# Lasers_Drivers_Design_Pingu_X1_pingu.net
KiCad netlist of a schematic drawn in EAGLE
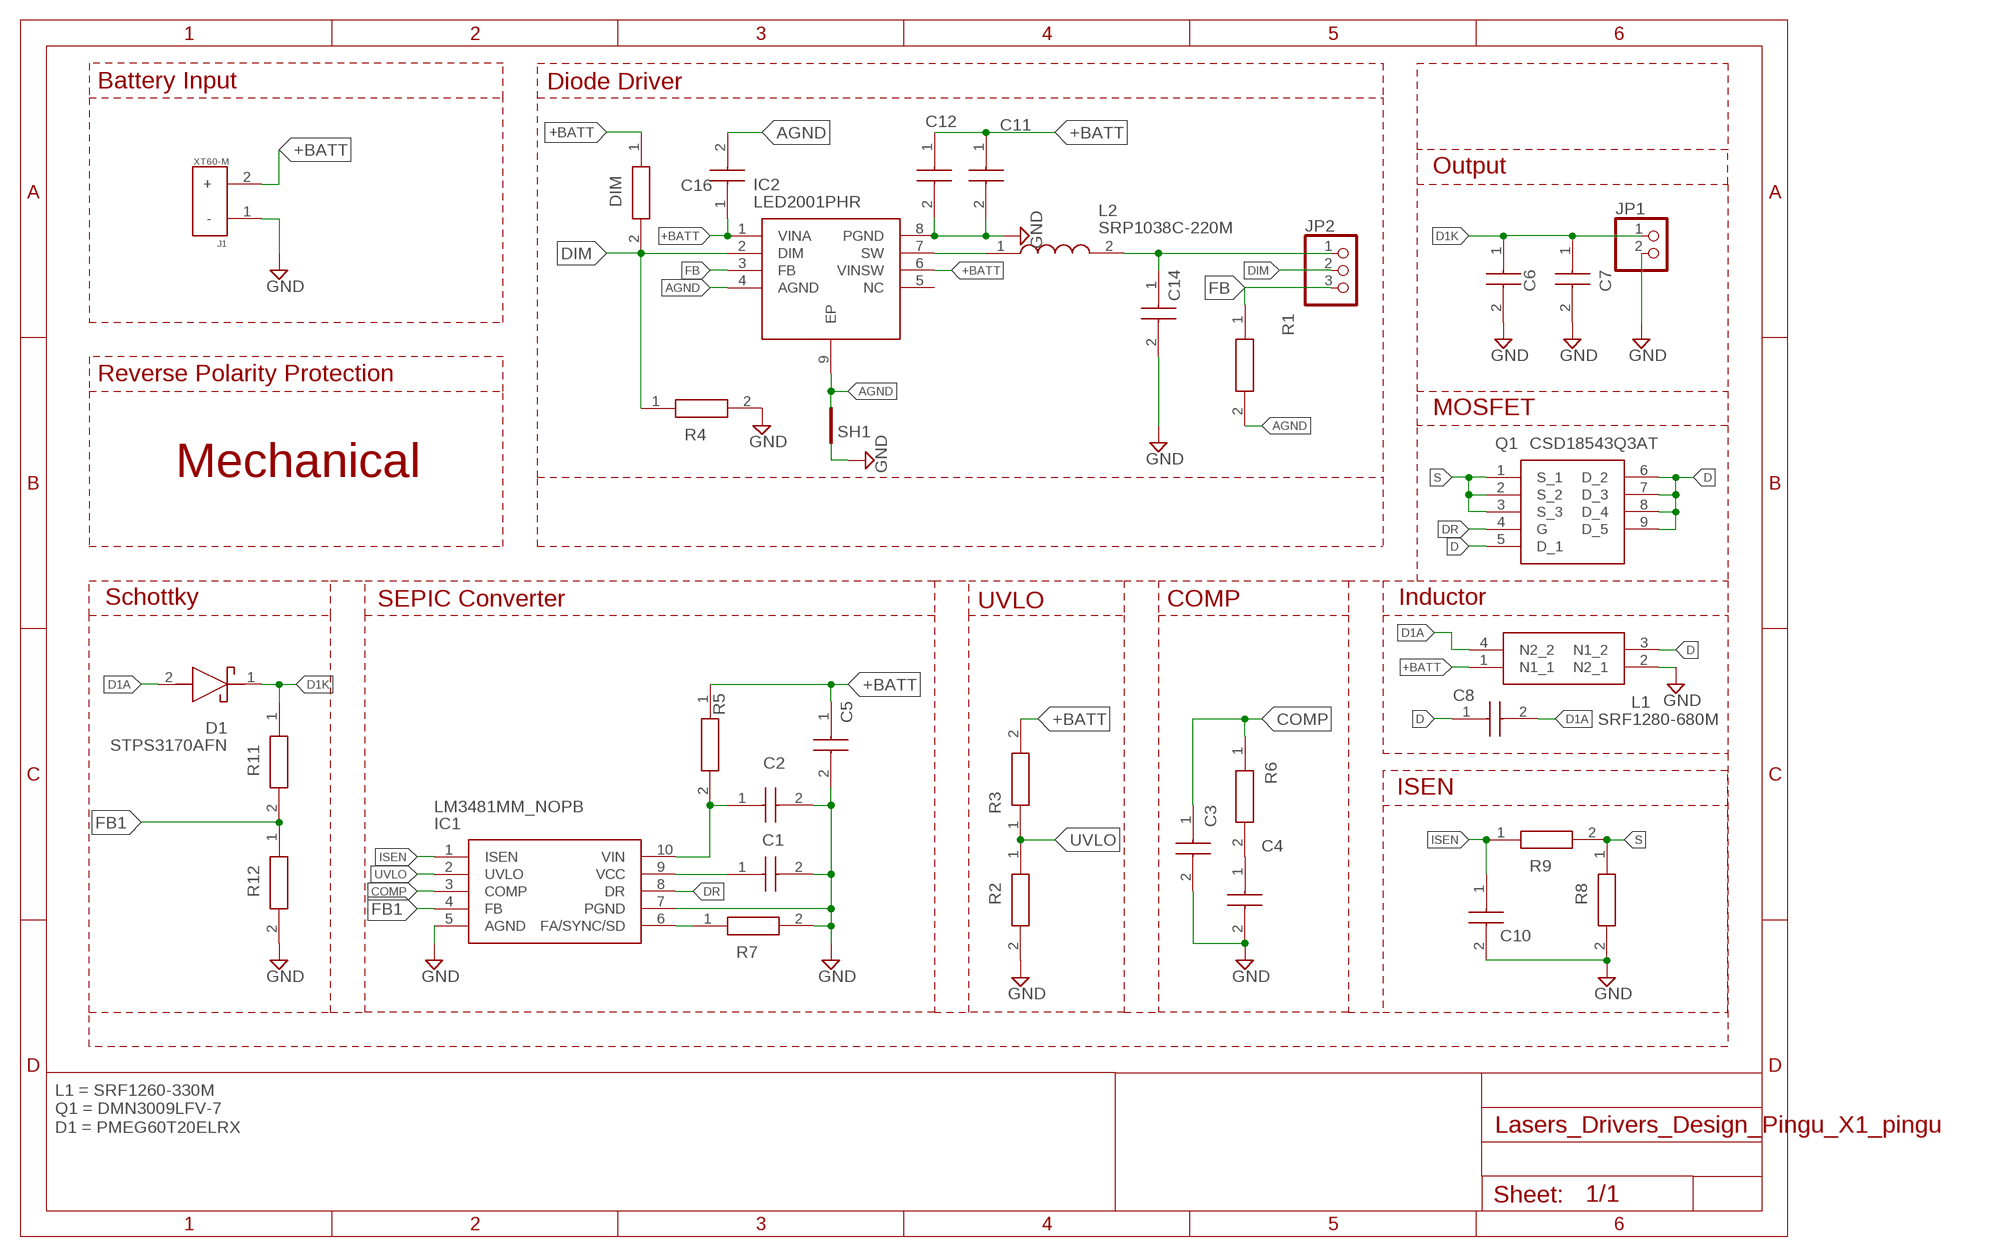
[diagram p0: schematic, sheet 1]

(export (version "E")
  (design (tool "Eeschema 10.0.6"))
  (components
    (comp (ref "C1")
      (value "GCM0335C1H8R0DA16J")
      (footprint "eagle-import:CAPC0603X33N")
      (fields (field (name "MOUSER_PART_NUMBER") "81-GCM0335C1H8R0DA6J"))
      (libsource (lib "eagle-import") (part "GCM0335C1H8R0DA16J"))
    )
    (comp (ref "C2")
      (value "GCM0335C1H8R0DA16J")
      (footprint "eagle-import:CAPC0603X33N")
      (fields (field (name "MOUSER_PART_NUMBER") "81-GCM0335C1H8R0DA6J"))
      (libsource (lib "eagle-import") (part "GCM0335C1H8R0DA16J"))
    )
    (comp (ref "C3")
      (value "GCM0335C1H8R0DA16J")
      (footprint "eagle-import:CAPC0603X33N")
      (fields (field (name "MOUSER_PART_NUMBER") "81-GCM0335C1H8R0DA6J"))
      (libsource (lib "eagle-import") (part "GCM0335C1H8R0DA16J"))
    )
    (comp (ref "C4")
      (value "GCM0335C1H8R0DA16J")
      (footprint "eagle-import:CAPC0603X33N")
      (fields (field (name "MOUSER_PART_NUMBER") "81-GCM0335C1H8R0DA6J"))
      (libsource (lib "eagle-import") (part "GCM0335C1H8R0DA16J"))
    )
    (comp (ref "C5")
      (value "C1206C475K5RACTU")
      (footprint "eagle-import:CAPC3216X180N")
      (fields (field (name "MOUSER_PART_NUMBER") "80-C1206C475K5R"))
      (libsource (lib "eagle-import") (part "C1206C475K5RACTU"))
    )
    (comp (ref "C6")
      (value "C1206C475K5RACTU")
      (footprint "eagle-import:CAPC3216X180N")
      (fields (field (name "MOUSER_PART_NUMBER") "80-C1206C475K5R"))
      (libsource (lib "eagle-import") (part "C1206C475K5RACTU"))
    )
    (comp (ref "C7")
      (value "C1206C475K5RACTU")
      (footprint "eagle-import:CAPC3216X180N")
      (fields (field (name "MOUSER_PART_NUMBER") "80-C1206C475K5R"))
      (libsource (lib "eagle-import") (part "C1206C475K5RACTU"))
    )
    (comp (ref "C8")
      (value "C1206C475K5RACTU")
      (footprint "eagle-import:CAPC3216X180N")
      (fields (field (name "MOUSER_PART_NUMBER") "80-C1206C475K5R"))
      (libsource (lib "eagle-import") (part "C1206C475K5RACTU"))
    )
    (comp (ref "C10")
      (value "GCM0335C1H8R0DA16J")
      (footprint "eagle-import:CAPC0603X33N")
      (fields (field (name "MOUSER_PART_NUMBER") "81-GCM0335C1H8R0DA6J"))
      (libsource (lib "eagle-import") (part "GCM0335C1H8R0DA16J"))
    )
    (comp (ref "C11")
      (value "GCM0335C1H8R0DA16J")
      (footprint "eagle-import:CAPC0603X33N")
      (fields (field (name "MOUSER_PART_NUMBER") "81-GCM0335C1H8R0DA6J"))
      (libsource (lib "eagle-import") (part "GCM0335C1H8R0DA16J"))
    )
    (comp (ref "C12")
      (value "GCM0335C1H8R0DA16J")
      (footprint "eagle-import:CAPC0603X33N")
      (fields (field (name "MOUSER_PART_NUMBER") "81-GCM0335C1H8R0DA6J"))
      (libsource (lib "eagle-import") (part "GCM0335C1H8R0DA16J"))
    )
    (comp (ref "C14")
      (value "C1206C475K5RACTU")
      (footprint "eagle-import:CAPC3216X180N")
      (fields (field (name "MOUSER_PART_NUMBER") "80-C1206C475K5R"))
      (libsource (lib "eagle-import") (part "C1206C475K5RACTU"))
    )
    (comp (ref "C16")
      (value "C1206C475K5RACTU")
      (footprint "eagle-import:CAPC3216X180N")
      (fields (field (name "MOUSER_PART_NUMBER") "80-C1206C475K5R"))
      (libsource (lib "eagle-import") (part "C1206C475K5RACTU"))
    )
    (comp (ref "D1")
      (value "STPS3170AFN")
      (footprint "eagle-import:SODFL5226X110N")
      (fields (field (name "MOUSER_PART_NUMBER") "511-STPS3170AFN"))
      (libsource (lib "eagle-import") (part "STPS3170AFN"))
    )
    (comp (ref "DIM")
      (value "ERJ-3BWFR100V")
      (footprint "eagle-import:RESC1608X55N")
      (fields (field (name "MOUSER_PART_NUMBER") "667-ERJ-3BWFR100V"))
      (libsource (lib "eagle-import") (part "ERJ-3BWFR100V"))
    )
    (comp (ref "IC1")
      (value "LM3481MM_NOPB")
      (footprint "eagle-import:SOP50P490X110-10N")
      (fields
        (field (name "ARROW_PART_NUMBER") "LM3481MM/NOPB")
        (field (name "MOUSER_PART_NUMBER") "926-LM3481MM/NOPB")
      )
      (libsource (lib "eagle-import") (part "LM3481MM_NOPB"))
    )
    (comp (ref "IC2")
      (value "LED2001PHR")
      (footprint "eagle-import:SOIC127P600X170-9N")
      (fields (field (name "MOUSER_PART_NUMBER") "511-LED2001PHR"))
      (libsource (lib "eagle-import") (part "LED2001PHR"))
    )
    (comp (ref "J1")
      (value "XT60-M")
      (footprint "eagle-import:AMASS_XT60-M")
      (fields (field (name "MF") "AMASS"))
      (libsource (lib "eagle-import") (part "XT60-M"))
    )
    (comp (ref "JP1")
      (value "PINHD-1X2")
      (footprint "eagle-import:1X02")
      (libsource (lib "eagle-import") (part "PINHD-1X2"))
    )
    (comp (ref "JP2")
      (value "PINHD-1X3")
      (footprint "eagle-import:1X03")
      (libsource (lib "eagle-import") (part "PINHD-1X3"))
    )
    (comp (ref "L1")
      (value "SRF1280-680M")
      (footprint "eagle-import:SRF1280680M")
      (fields (field (name "MOUSER_PART_NUMBER") "652-SRF1280-680M") (field (name "SPICEPREFIX") "E"))
      (libsource (lib "eagle-import") (part "SRF1280-680M"))
    )
    (comp (ref "L2")
      (value "SRP1038C-220M")
      (footprint "eagle-import:INDPM110100X420N")
      (fields (field (name "MOUSER_PART_NUMBER") "652-SRP1038C-220M"))
      (libsource (lib "eagle-import") (part "SRP1038C-220M"))
    )
    (comp (ref "Q1")
      (value "CSD18543Q3AT")
      (footprint "eagle-import:CSD18543Q3AT")
      (fields (field (name "MOUSER_PART_NUMBER") "595-CSD18543Q3AT"))
      (libsource (lib "eagle-import") (part "CSD18543Q3AT"))
    )
    (comp (ref "R1")
      (value "ERJ-3BWFR100V")
      (footprint "eagle-import:RESC1608X55N")
      (fields (field (name "MOUSER_PART_NUMBER") "667-ERJ-3BWFR100V"))
      (libsource (lib "eagle-import") (part "ERJ-3BWFR100V"))
    )
    (comp (ref "R2")
      (value "ERJ-3BWFR100V")
      (footprint "eagle-import:RESC1608X55N")
      (fields (field (name "MOUSER_PART_NUMBER") "667-ERJ-3BWFR100V"))
      (libsource (lib "eagle-import") (part "ERJ-3BWFR100V"))
    )
    (comp (ref "R3")
      (value "ERJ-3BWFR100V")
      (footprint "eagle-import:RESC1608X55N")
      (fields (field (name "MOUSER_PART_NUMBER") "667-ERJ-3BWFR100V"))
      (libsource (lib "eagle-import") (part "ERJ-3BWFR100V"))
    )
    (comp (ref "R4")
      (value "ERJ-3BWFR100V")
      (footprint "eagle-import:RESC1608X55N")
      (fields (field (name "MOUSER_PART_NUMBER") "667-ERJ-3BWFR100V"))
      (libsource (lib "eagle-import") (part "ERJ-3BWFR100V"))
    )
    (comp (ref "R5")
      (value "ERJ-3BWFR100V")
      (footprint "eagle-import:RESC1608X55N")
      (fields (field (name "MOUSER_PART_NUMBER") "667-ERJ-3BWFR100V"))
      (libsource (lib "eagle-import") (part "ERJ-3BWFR100V"))
    )
    (comp (ref "R6")
      (value "ERJ-3BWFR100V")
      (footprint "eagle-import:RESC1608X55N")
      (fields (field (name "MOUSER_PART_NUMBER") "667-ERJ-3BWFR100V"))
      (libsource (lib "eagle-import") (part "ERJ-3BWFR100V"))
    )
    (comp (ref "R7")
      (value "ERJ-3BWFR100V")
      (footprint "eagle-import:RESC1608X55N")
      (fields (field (name "MOUSER_PART_NUMBER") "667-ERJ-3BWFR100V"))
      (libsource (lib "eagle-import") (part "ERJ-3BWFR100V"))
    )
    (comp (ref "R8")
      (value "ERJ-3BWFR100V")
      (footprint "eagle-import:RESC1608X55N")
      (fields (field (name "MOUSER_PART_NUMBER") "667-ERJ-3BWFR100V"))
      (libsource (lib "eagle-import") (part "ERJ-3BWFR100V"))
    )
    (comp (ref "R9")
      (value "ERJ-3BWFR100V")
      (footprint "eagle-import:RESC1608X55N")
      (fields (field (name "MOUSER_PART_NUMBER") "667-ERJ-3BWFR100V"))
      (libsource (lib "eagle-import") (part "ERJ-3BWFR100V"))
    )
    (comp (ref "R11")
      (value "ERJ-3BWFR100V")
      (footprint "eagle-import:RESC1608X55N")
      (fields (field (name "MOUSER_PART_NUMBER") "667-ERJ-3BWFR100V"))
      (libsource (lib "eagle-import") (part "ERJ-3BWFR100V"))
    )
    (comp (ref "R12")
      (value "ERJ-3BWFR100V")
      (footprint "eagle-import:RESC1608X55N")
      (fields (field (name "MOUSER_PART_NUMBER") "667-ERJ-3BWFR100V"))
      (libsource (lib "eagle-import") (part "ERJ-3BWFR100V"))
    )
    (comp (ref "SH1")
      (value "SHORTT5")
      (footprint "eagle-import:SHORT_TOP-50")
      (libsource (lib "eagle-import") (part "SHORTT5"))
    )
  )
  (nets
    (net (code "1") (name "+BATT") (class "Default")
      (node (ref "C11") (pin "1") (pinfunction "1_1") (pintype "bidirectional"))
      (node (ref "C12") (pin "1") (pinfunction "1_1") (pintype "bidirectional"))
      (node (ref "C16") (pin "1") (pinfunction "1_1") (pintype "bidirectional"))
      (node (ref "C5") (pin "1") (pinfunction "1_1") (pintype "bidirectional"))
      (node (ref "DIM") (pin "1") (pinfunction "1_1") (pintype "bidirectional"))
      (node (ref "IC2") (pin "1") (pinfunction "VINA_1") (pintype "input"))
      (node (ref "IC2") (pin "6") (pinfunction "VINSW_6") (pintype "input"))
      (node (ref "J1") (pin "2") (pinfunction "+_2") (pintype "passive"))
      (node (ref "L1") (pin "1") (pinfunction "N1_1_1") (pintype "bidirectional"))
      (node (ref "R3") (pin "2") (pinfunction "2_2") (pintype "bidirectional"))
      (node (ref "R5") (pin "1") (pinfunction "1_1") (pintype "bidirectional"))
    )
    (net (code "2") (name "AGND") (class "Default")
      (node (ref "C16") (pin "2") (pinfunction "2_2") (pintype "bidirectional"))
      (node (ref "IC2") (pin "4") (pinfunction "AGND_4") (pintype "power_in"))
      (node (ref "IC2") (pin "9") (pinfunction "EP_9") (pintype "power_in"))
      (node (ref "R1") (pin "2") (pinfunction "2_2") (pintype "bidirectional"))
      (node (ref "SH1") (pin "2") (pinfunction "P$2_2") (pintype "bidirectional"))
    )
    (net (code "3") (name "COMP") (class "Default")
      (node (ref "C3") (pin "1") (pinfunction "1_1") (pintype "bidirectional"))
      (node (ref "IC1") (pin "3") (pinfunction "COMP_3") (pintype "bidirectional"))
      (node (ref "R6") (pin "1") (pinfunction "1_1") (pintype "bidirectional"))
    )
    (net (code "4") (name "D") (class "Default")
      (node (ref "C8") (pin "1") (pinfunction "1_1") (pintype "bidirectional"))
      (node (ref "L1") (pin "3") (pinfunction "N1_2_3") (pintype "bidirectional"))
      (node (ref "Q1") (pin "5") (pinfunction "D_1_5") (pintype "bidirectional"))
      (node (ref "Q1") (pin "6") (pinfunction "D_2_6") (pintype "bidirectional"))
      (node (ref "Q1") (pin "7") (pinfunction "D_3_7") (pintype "bidirectional"))
      (node (ref "Q1") (pin "8") (pinfunction "D_4_8") (pintype "bidirectional"))
      (node (ref "Q1") (pin "9") (pinfunction "D_5_9") (pintype "bidirectional"))
    )
    (net (code "5") (name "D1A") (class "Default")
      (node (ref "C8") (pin "2") (pinfunction "2_2") (pintype "bidirectional"))
      (node (ref "D1") (pin "2") (pinfunction "A_2") (pintype "bidirectional"))
      (node (ref "L1") (pin "4") (pinfunction "N2_2_4") (pintype "bidirectional"))
    )
    (net (code "6") (name "D1K") (class "Default")
      (node (ref "C6") (pin "1") (pinfunction "1_1") (pintype "bidirectional"))
      (node (ref "C7") (pin "1") (pinfunction "1_1") (pintype "bidirectional"))
      (node (ref "D1") (pin "1") (pinfunction "K_1") (pintype "bidirectional"))
      (node (ref "JP1") (pin "1") (pinfunction "1_1") (pintype "passive"))
      (node (ref "R11") (pin "1") (pinfunction "1_1") (pintype "bidirectional"))
    )
    (net (code "7") (name "DIM") (class "Default")
      (node (ref "DIM") (pin "2") (pinfunction "2_2") (pintype "bidirectional"))
      (node (ref "IC2") (pin "2") (pinfunction "DIM_2") (pintype "bidirectional"))
      (node (ref "JP2") (pin "2") (pinfunction "2_2") (pintype "passive"))
      (node (ref "R4") (pin "1") (pinfunction "1_1") (pintype "bidirectional"))
    )
    (net (code "8") (name "DR") (class "Default")
      (node (ref "IC1") (pin "8") (pinfunction "DR_8") (pintype "bidirectional"))
      (node (ref "Q1") (pin "4") (pinfunction "G_4") (pintype "bidirectional"))
    )
    (net (code "9") (name "FB") (class "Default")
      (node (ref "IC2") (pin "3") (pinfunction "FB_3") (pintype "bidirectional"))
      (node (ref "JP2") (pin "3") (pinfunction "3_3") (pintype "passive"))
      (node (ref "R1") (pin "1") (pinfunction "1_1") (pintype "bidirectional"))
    )
    (net (code "10") (name "FB1") (class "Default")
      (node (ref "IC1") (pin "4") (pinfunction "FB_4") (pintype "bidirectional"))
      (node (ref "R11") (pin "2") (pinfunction "2_2") (pintype "bidirectional"))
      (node (ref "R12") (pin "1") (pinfunction "1_1") (pintype "bidirectional"))
    )
    (net (code "11") (name "GND") (class "Default")
      (node (ref "C1") (pin "2") (pinfunction "2_2") (pintype "bidirectional"))
      (node (ref "C10") (pin "2") (pinfunction "2_2") (pintype "bidirectional"))
      (node (ref "C11") (pin "2") (pinfunction "2_2") (pintype "bidirectional"))
      (node (ref "C12") (pin "2") (pinfunction "2_2") (pintype "bidirectional"))
      (node (ref "C14") (pin "2") (pinfunction "2_2") (pintype "bidirectional"))
      (node (ref "C2") (pin "2") (pinfunction "2_2") (pintype "bidirectional"))
      (node (ref "C3") (pin "2") (pinfunction "2_2") (pintype "bidirectional"))
      (node (ref "C4") (pin "2") (pinfunction "2_2") (pintype "bidirectional"))
      (node (ref "C5") (pin "2") (pinfunction "2_2") (pintype "bidirectional"))
      (node (ref "C6") (pin "2") (pinfunction "2_2") (pintype "bidirectional"))
      (node (ref "C7") (pin "2") (pinfunction "2_2") (pintype "bidirectional"))
      (node (ref "IC1") (pin "5") (pinfunction "AGND_5") (pintype "bidirectional"))
      (node (ref "IC1") (pin "7") (pinfunction "PGND_7") (pintype "bidirectional"))
      (node (ref "IC2") (pin "8") (pinfunction "PGND_8") (pintype "power_in"))
      (node (ref "J1") (pin "1") (pinfunction "-_1") (pintype "passive"))
      (node (ref "JP1") (pin "2") (pinfunction "2_2") (pintype "passive"))
      (node (ref "L1") (pin "2") (pinfunction "N2_1_2") (pintype "bidirectional"))
      (node (ref "R12") (pin "2") (pinfunction "2_2") (pintype "bidirectional"))
      (node (ref "R2") (pin "2") (pinfunction "2_2") (pintype "bidirectional"))
      (node (ref "R4") (pin "2") (pinfunction "2_2") (pintype "bidirectional"))
      (node (ref "R7") (pin "2") (pinfunction "2_2") (pintype "bidirectional"))
      (node (ref "R8") (pin "2") (pinfunction "2_2") (pintype "bidirectional"))
      (node (ref "SH1") (pin "1") (pinfunction "P$1_1") (pintype "bidirectional"))
    )
    (net (code "12") (name "ISEN") (class "Default")
      (node (ref "C10") (pin "1") (pinfunction "1_1") (pintype "bidirectional"))
      (node (ref "IC1") (pin "1") (pinfunction "ISEN_1") (pintype "bidirectional"))
      (node (ref "R9") (pin "1") (pinfunction "1_1") (pintype "bidirectional"))
    )
    (net (code "13") (name "Net-(C4-Pad1)") (class "Default")
      (node (ref "C4") (pin "1") (pinfunction "1_1") (pintype "bidirectional"))
      (node (ref "R6") (pin "2") (pinfunction "2_2") (pintype "bidirectional"))
    )
    (net (code "14") (name "Net-(C14-Pad1)") (class "Default")
      (node (ref "C14") (pin "1") (pinfunction "1_1") (pintype "bidirectional"))
      (node (ref "JP2") (pin "1") (pinfunction "1_1") (pintype "passive"))
      (node (ref "L2") (pin "2") (pinfunction "2_2") (pintype "bidirectional"))
    )
    (net (code "15") (name "Net-(IC1-FA{slash}SYNC{slash}SD)") (class "Default")
      (node (ref "IC1") (pin "6") (pinfunction "FA/SYNC/SD_6") (pintype "bidirectional"))
      (node (ref "R7") (pin "1") (pinfunction "1_1") (pintype "bidirectional"))
    )
    (net (code "16") (name "Net-(IC1-VCC)") (class "Default")
      (node (ref "C1") (pin "1") (pinfunction "1_1") (pintype "bidirectional"))
      (node (ref "IC1") (pin "9") (pinfunction "VCC_9") (pintype "bidirectional"))
    )
    (net (code "17") (name "Net-(IC1-VIN)") (class "Default")
      (node (ref "C2") (pin "1") (pinfunction "1_1") (pintype "bidirectional"))
      (node (ref "IC1") (pin "10") (pinfunction "VIN_10") (pintype "bidirectional"))
      (node (ref "R5") (pin "2") (pinfunction "2_2") (pintype "bidirectional"))
    )
    (net (code "18") (name "Net-(IC2-SW)") (class "Default")
      (node (ref "IC2") (pin "7") (pinfunction "SW_7") (pintype "bidirectional"))
      (node (ref "L2") (pin "1") (pinfunction "1_1") (pintype "bidirectional"))
    )
    (net (code "19") (name "S") (class "Default")
      (node (ref "Q1") (pin "1") (pinfunction "S_1_1") (pintype "bidirectional"))
      (node (ref "Q1") (pin "2") (pinfunction "S_2_2") (pintype "bidirectional"))
      (node (ref "Q1") (pin "3") (pinfunction "S_3_3") (pintype "bidirectional"))
      (node (ref "R8") (pin "1") (pinfunction "1_1") (pintype "bidirectional"))
      (node (ref "R9") (pin "2") (pinfunction "2_2") (pintype "bidirectional"))
    )
    (net (code "20") (name "UVLO") (class "Default")
      (node (ref "IC1") (pin "2") (pinfunction "UVLO_2") (pintype "bidirectional"))
      (node (ref "R2") (pin "1") (pinfunction "1_1") (pintype "bidirectional"))
      (node (ref "R3") (pin "1") (pinfunction "1_1") (pintype "bidirectional"))
    )
    (net (code "21") (name "unconnected-(IC2-NC-Pad5)") (class "Default")
      (node (ref "IC2") (pin "5") (pinfunction "NC_5") (pintype "no_connect"))
    )
  )
)
